# Wearable_sensor_v2_0.net
KiCad netlist of a schematic drawn in Altium Designer
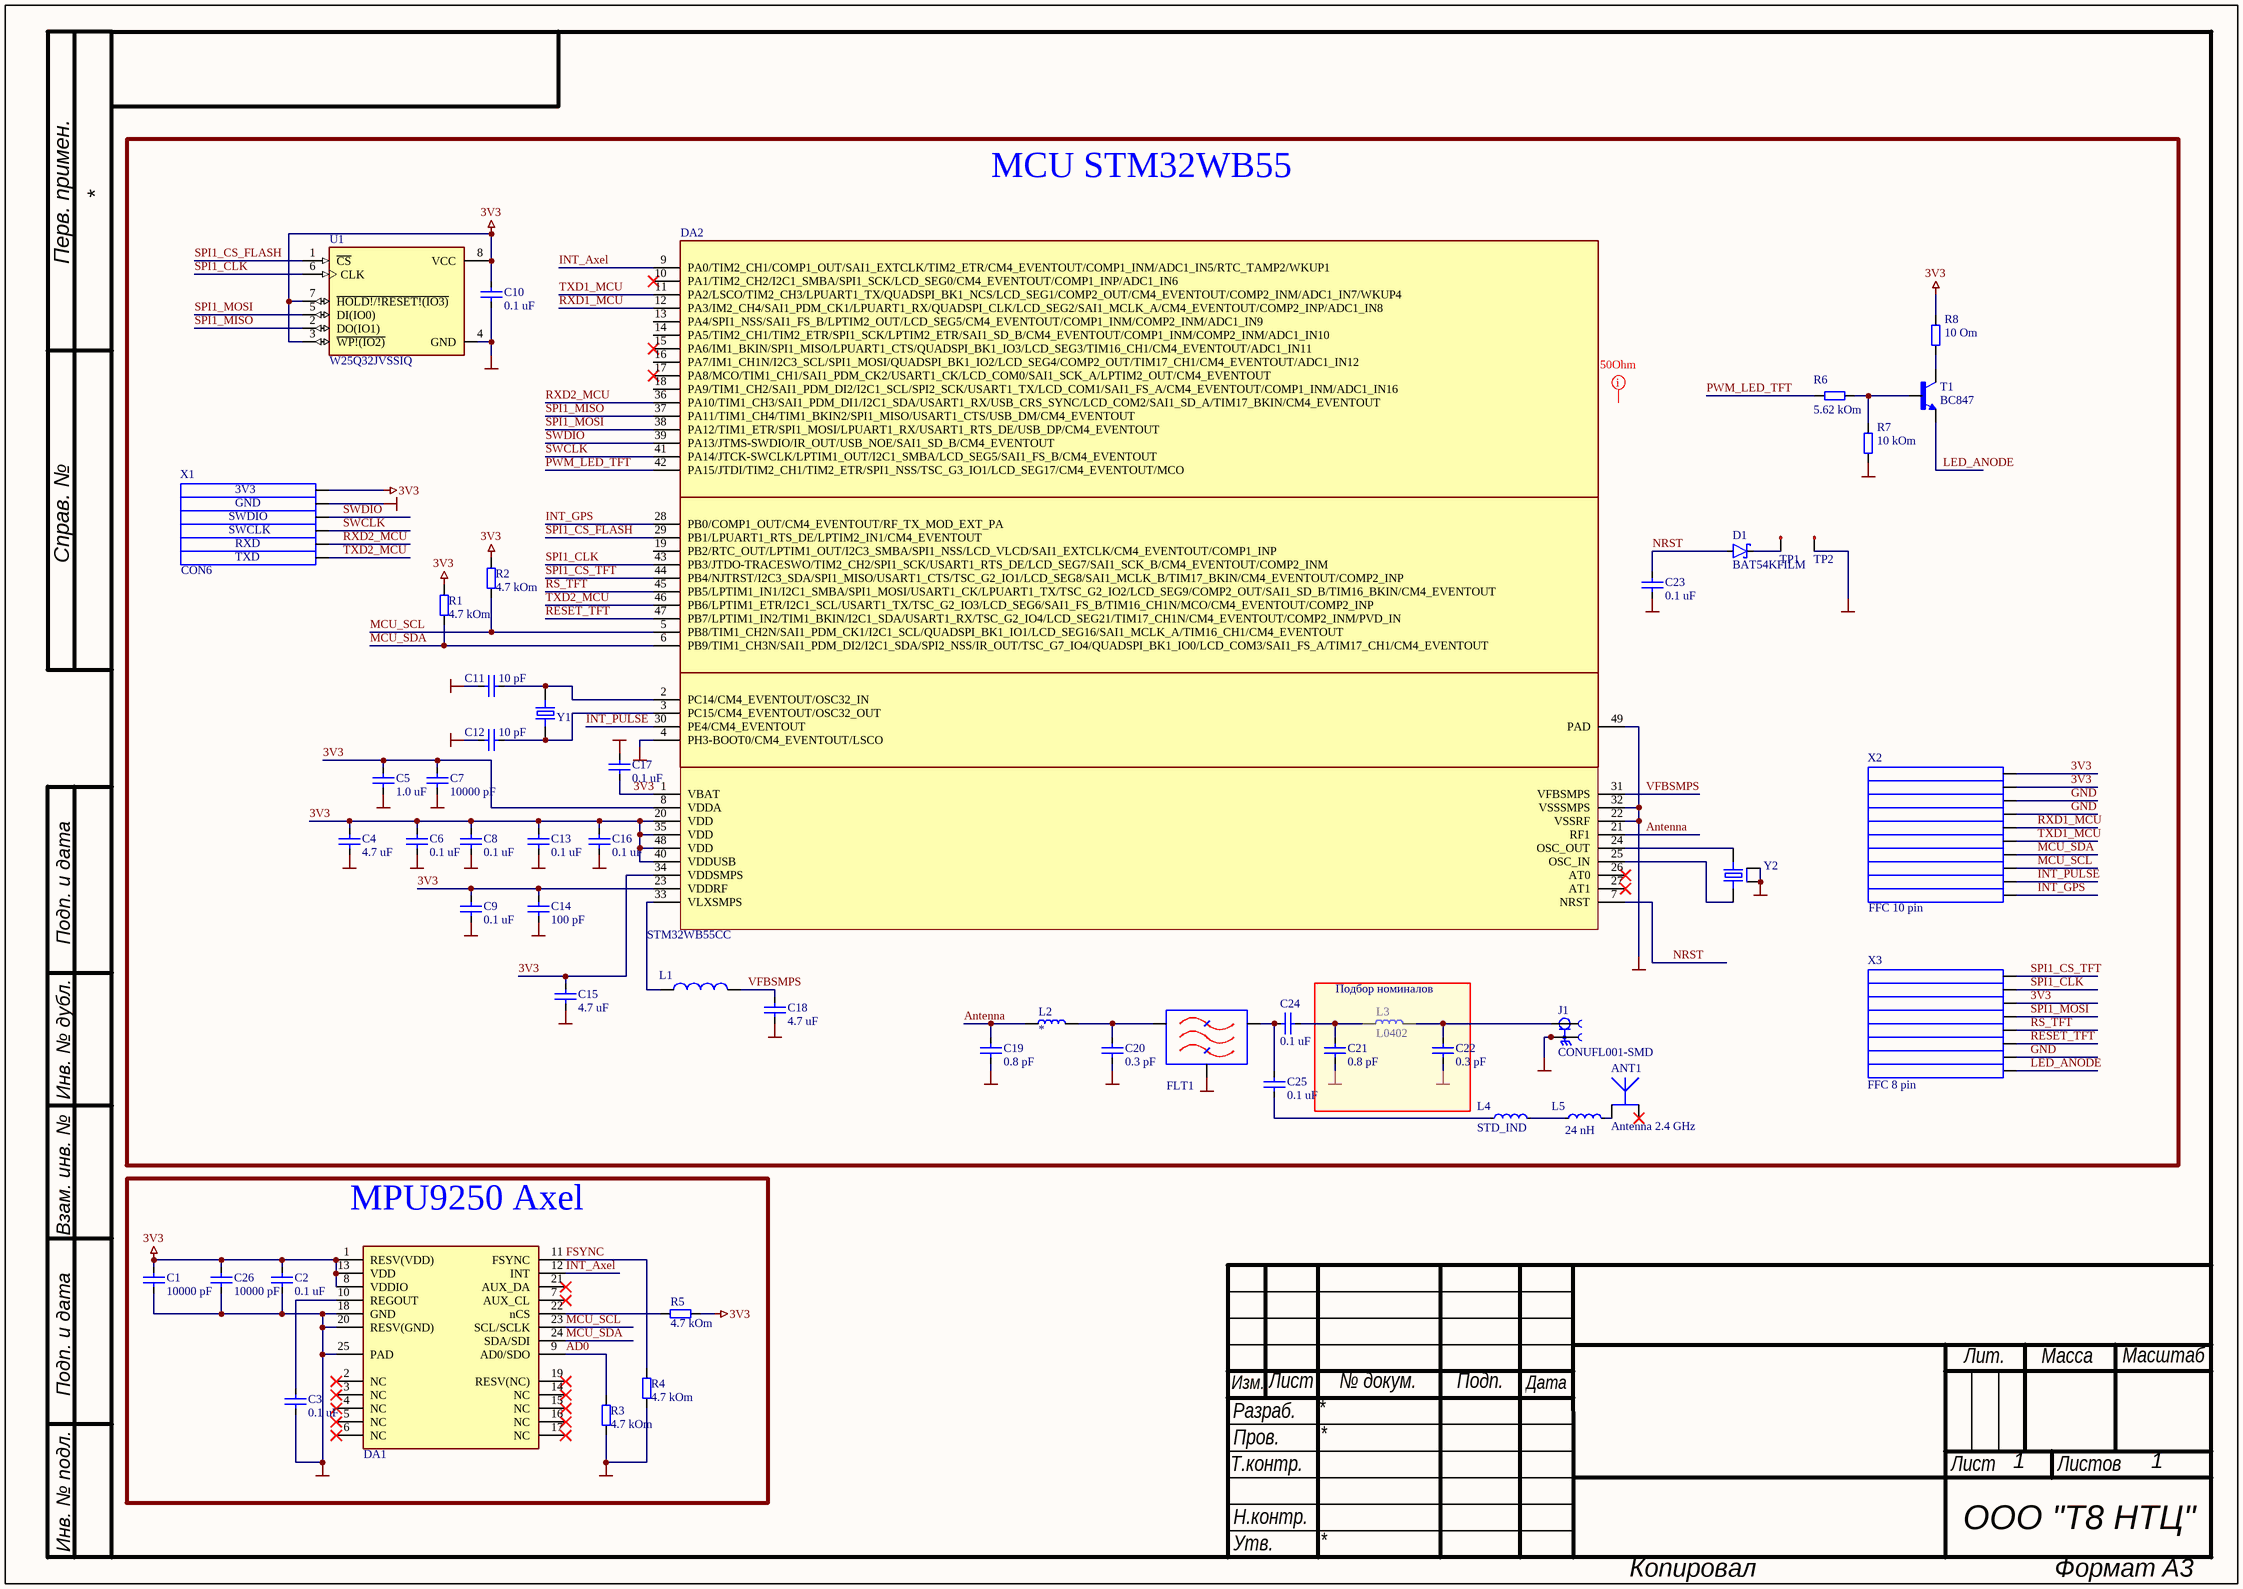
[diagram p0: Wearable_sensor_v2.0.SchDoc]

(export (version "E")
  (design (tool "Eeschema 10.0.6"))
  (components
    (comp (ref "ANT1")
      (value "Antenna 2.4 GHz")
      (footprint "RFANT3216120A5T")
      (libsource (lib "SCH_Wearing_sensor") (part "Antenna 2.4"))
    )
    (comp (ref "C1")
      (value "10000 pF")
      (footprint "CAPC1005X55N")
      (fields
        (field (name "MANUFACTURERPARTNUMBER") "GRM155R71H103KA88D")
        (field (name "MANUFACTURER") "muRata")
        (field (name "Comment") "STD_CAP")
        (field (name "AUTHORMODIFICATION_COMP") "anosova")
      )
      (libsource (lib "Altium_lib") (part "STD_CAP"))
    )
    (comp (ref "C2")
      (value "0.1 uF")
      (footprint "CAPC1005X55N")
      (fields
        (field (name "MANUFACTURERPARTNUMBER") "GRM155R71H104KE14D")
        (field (name "MANUFACTURER") "muRata")
        (field (name "Comment") "STD_CAP")
        (field (name "AUTHORCREATION_COMP") "altium_lib_sch_p")
        (field (name "AUTHORMODIFICATION_COMP") "anosova")
      )
      (libsource (lib "Altium_lib") (part "STD_CAP"))
    )
    (comp (ref "C3")
      (value "0.1 uF")
      (footprint "CAPC1005X55N")
      (fields
        (field (name "MANUFACTURERPARTNUMBER") "GRM155R71H104KE14D")
        (field (name "MANUFACTURER") "muRata")
        (field (name "Comment") "STD_CAP")
        (field (name "AUTHORCREATION_COMP") "altium_lib_sch_p")
        (field (name "AUTHORMODIFICATION_COMP") "anosova")
      )
      (libsource (lib "Altium_lib") (part "STD_CAP"))
    )
    (comp (ref "C4")
      (value "4.7 uF")
      (footprint "CAPC1005X55N")
      (fields
        (field (name "MANUFACTURERPARTNUMBER") "GRM155R60J475M")
        (field (name "MANUFACTURER") "muRata")
        (field (name "Comment") "STD_CAP")
        (field (name "AUTHORCREATION_COMP") "asergeev")
        (field (name "AUTHORMODIFICATION_COMP") "anosova")
      )
      (libsource (lib "Altium_lib") (part "STD_CAP"))
    )
    (comp (ref "C5")
      (value "1.0 uF")
      (footprint "CAPC1005X55N")
      (fields
        (field (name "MANUFACTURERPARTNUMBER") "GRM155R61A105K")
        (field (name "MANUFACTURER") "muRata")
        (field (name "Comment") "STD_CAP")
        (field (name "AUTHORCREATION_COMP") "asergeev")
        (field (name "AUTHORMODIFICATION_COMP") "anosova")
      )
      (libsource (lib "Altium_lib") (part "STD_CAP"))
    )
    (comp (ref "C6")
      (value "0.1 uF")
      (footprint "CAPC1005X55N")
      (fields
        (field (name "MANUFACTURERPARTNUMBER") "GRM155R71H104KE14D")
        (field (name "MANUFACTURER") "muRata")
        (field (name "Comment") "STD_CAP")
        (field (name "AUTHORCREATION_COMP") "altium_lib_sch_p")
        (field (name "AUTHORMODIFICATION_COMP") "anosova")
      )
      (libsource (lib "Altium_lib") (part "STD_CAP"))
    )
    (comp (ref "C7")
      (value "10000 pF")
      (footprint "CAPC1005X55N")
      (fields
        (field (name "MANUFACTURERPARTNUMBER") "GRM155R71H103KA88D")
        (field (name "MANUFACTURER") "muRata")
        (field (name "Comment") "STD_CAP")
        (field (name "AUTHORMODIFICATION_COMP") "anosova")
      )
      (libsource (lib "Altium_lib") (part "STD_CAP"))
    )
    (comp (ref "C8")
      (value "0.1 uF")
      (footprint "CAPC1005X55N")
      (fields
        (field (name "MANUFACTURERPARTNUMBER") "GRM155R71H104KE14D")
        (field (name "MANUFACTURER") "muRata")
        (field (name "Comment") "STD_CAP")
        (field (name "AUTHORCREATION_COMP") "altium_lib_sch_p")
        (field (name "AUTHORMODIFICATION_COMP") "anosova")
      )
      (libsource (lib "Altium_lib") (part "STD_CAP"))
    )
    (comp (ref "C9")
      (value "0.1 uF")
      (footprint "CAPC1005X55N")
      (fields
        (field (name "MANUFACTURERPARTNUMBER") "GRM155R71H104KE14D")
        (field (name "MANUFACTURER") "muRata")
        (field (name "Comment") "STD_CAP")
        (field (name "AUTHORCREATION_COMP") "altium_lib_sch_p")
        (field (name "AUTHORMODIFICATION_COMP") "anosova")
      )
      (libsource (lib "Altium_lib") (part "STD_CAP"))
    )
    (comp (ref "C10")
      (value "0.1 uF")
      (footprint "CAPC1005X55N")
      (fields
        (field (name "MANUFACTURERPARTNUMBER") "GRM155R71H104KE14D")
        (field (name "MANUFACTURER") "muRata")
        (field (name "Comment") "STD_CAP")
        (field (name "AUTHORCREATION_COMP") "altium_lib_sch_p")
        (field (name "AUTHORMODIFICATION_COMP") "anosova")
      )
      (libsource (lib "Altium_lib") (part "STD_CAP"))
    )
    (comp (ref "C11")
      (value "10 pF")
      (footprint "CAPC1005X55N")
      (fields
        (field (name "MANUFACTURERPARTNUMBER") "GRM1555C1H100GA01D")
        (field (name "MANUFACTURER") "muRata")
        (field (name "Comment") "STD_CAP")
        (field (name "AUTHORMODIFICATION_COMP") "anosova")
      )
      (libsource (lib "Altium_lib") (part "STD_CAP"))
    )
    (comp (ref "C12")
      (value "10 pF")
      (footprint "CAPC1005X55N")
      (fields
        (field (name "MANUFACTURERPARTNUMBER") "GRM1555C1H100GA01D")
        (field (name "MANUFACTURER") "muRata")
        (field (name "Comment") "STD_CAP")
        (field (name "AUTHORMODIFICATION_COMP") "anosova")
      )
      (libsource (lib "Altium_lib") (part "STD_CAP"))
    )
    (comp (ref "C13")
      (value "0.1 uF")
      (footprint "CAPC1005X55N")
      (fields
        (field (name "MANUFACTURERPARTNUMBER") "GRM155R71H104KE14D")
        (field (name "MANUFACTURER") "muRata")
        (field (name "Comment") "STD_CAP")
        (field (name "AUTHORCREATION_COMP") "altium_lib_sch_p")
        (field (name "AUTHORMODIFICATION_COMP") "anosova")
      )
      (libsource (lib "Altium_lib") (part "STD_CAP"))
    )
    (comp (ref "C14")
      (value "100 pF")
      (footprint "CAPC1005X55N")
      (fields
        (field (name "MANUFACTURERPARTNUMBER") "GRM1555C1H101GA01D")
        (field (name "MANUFACTURER") "muRata")
        (field (name "Comment") "STD_CAP")
        (field (name "AUTHORMODIFICATION_COMP") "anosova")
      )
      (libsource (lib "Altium_lib") (part "STD_CAP"))
    )
    (comp (ref "C15")
      (value "4.7 uF")
      (footprint "CAPC1005X55N")
      (fields
        (field (name "MANUFACTURERPARTNUMBER") "GRM155R60J475M")
        (field (name "MANUFACTURER") "muRata")
        (field (name "Comment") "STD_CAP")
        (field (name "AUTHORCREATION_COMP") "asergeev")
        (field (name "AUTHORMODIFICATION_COMP") "anosova")
      )
      (libsource (lib "Altium_lib") (part "STD_CAP"))
    )
    (comp (ref "C16")
      (value "0.1 uF")
      (footprint "CAPC1005X55N")
      (fields
        (field (name "MANUFACTURERPARTNUMBER") "GRM155R71H104KE14D")
        (field (name "MANUFACTURER") "muRata")
        (field (name "Comment") "STD_CAP")
        (field (name "AUTHORCREATION_COMP") "altium_lib_sch_p")
        (field (name "AUTHORMODIFICATION_COMP") "anosova")
      )
      (libsource (lib "Altium_lib") (part "STD_CAP"))
    )
    (comp (ref "C17")
      (value "0.1 uF")
      (footprint "CAPC1005X55N")
      (fields
        (field (name "MANUFACTURERPARTNUMBER") "GRM155R71H104KE14D")
        (field (name "MANUFACTURER") "muRata")
        (field (name "Comment") "STD_CAP")
        (field (name "AUTHORCREATION_COMP") "altium_lib_sch_p")
        (field (name "AUTHORMODIFICATION_COMP") "anosova")
      )
      (libsource (lib "Altium_lib") (part "STD_CAP"))
    )
    (comp (ref "C18")
      (value "4.7 uF")
      (footprint "CAPC1005X55N")
      (fields
        (field (name "MANUFACTURERPARTNUMBER") "GRM155R60J475M")
        (field (name "MANUFACTURER") "muRata")
        (field (name "Comment") "STD_CAP")
        (field (name "AUTHORCREATION_COMP") "asergeev")
        (field (name "AUTHORMODIFICATION_COMP") "anosova")
      )
      (libsource (lib "Altium_lib") (part "STD_CAP"))
    )
    (comp (ref "C19")
      (value "0.8 pF")
      (footprint "CAPC1005X55N")
      (fields
        (field (name "MANUFACTURERPARTNUMBER") "GRM1555C1HR80WA01D")
        (field (name "MANUFACTURER") "muRata")
        (field (name "Comment") "STD_CAP")
        (field (name "AUTHORMODIFICATION_COMP") "anosova")
      )
      (libsource (lib "Altium_lib") (part "STD_CAP"))
    )
    (comp (ref "C20")
      (value "0.3 pF")
      (footprint "CAPC1005X55N")
      (fields
        (field (name "MANUFACTURERPARTNUMBER") "GRM1555C1HR30WA01D")
        (field (name "MANUFACTURER") "muRata")
        (field (name "Comment") "STD_CAP")
        (field (name "AUTHORMODIFICATION_COMP") "anosova")
      )
      (libsource (lib "Altium_lib") (part "STD_CAP"))
    )
    (comp (ref "C21")
      (value "0.8 pF")
      (footprint "CAPC1005X55N")
      (fields
        (field (name "MANUFACTURERPARTNUMBER") "GRM1555C1HR80WA01D")
        (field (name "MANUFACTURER") "muRata")
        (field (name "Comment") "STD_CAP")
        (field (name "AUTHORMODIFICATION_COMP") "anosova")
      )
      (libsource (lib "Altium_lib") (part "STD_CAP"))
    )
    (comp (ref "C22")
      (value "0.3 pF")
      (footprint "CAPC1005X55N")
      (fields
        (field (name "MANUFACTURERPARTNUMBER") "GRM1555C1HR30WA01D")
        (field (name "MANUFACTURER") "muRata")
        (field (name "Comment") "STD_CAP")
        (field (name "AUTHORMODIFICATION_COMP") "anosova")
      )
      (libsource (lib "Altium_lib") (part "STD_CAP"))
    )
    (comp (ref "C23")
      (value "0.1 uF")
      (footprint "CAPC1005X55N")
      (fields
        (field (name "MANUFACTURERPARTNUMBER") "GRM155R71H104KE14D")
        (field (name "MANUFACTURER") "muRata")
        (field (name "Comment") "STD_CAP")
        (field (name "AUTHORCREATION_COMP") "altium_lib_sch_p")
        (field (name "AUTHORMODIFICATION_COMP") "anosova")
      )
      (libsource (lib "Altium_lib") (part "STD_CAP"))
    )
    (comp (ref "C24")
      (value "0.1 uF")
      (footprint "CAPC1005X55N")
      (fields
        (field (name "MANUFACTURERPARTNUMBER") "CC0402KRX7R8BB104")
        (field (name "MANUFACTURER") "Yageo")
        (field (name "Comment") "STD_CAP")
        (field (name "AUTHORCREATION_COMP") "anosova")
        (field (name "AUTHORMODIFICATION_COMP") "anosova")
      )
      (libsource (lib "Altium_lib") (part "STD_CAP"))
    )
    (comp (ref "C25")
      (value "0.1 uF")
      (footprint "CAPC1005X55N")
      (fields
        (field (name "MANUFACTURERPARTNUMBER") "CC0402KRX7R8BB104")
        (field (name "MANUFACTURER") "Yageo")
        (field (name "Comment") "STD_CAP")
        (field (name "AUTHORCREATION_COMP") "anosova")
        (field (name "AUTHORMODIFICATION_COMP") "anosova")
      )
      (libsource (lib "Altium_lib") (part "STD_CAP"))
    )
    (comp (ref "C26")
      (value "10000 pF")
      (footprint "CAPC1005X55N:CAPC1005X55N")
      (fields
        (field (name "MANUFACTURERPARTNUMBER") "GRM155R71H103KA88D")
        (field (name "MANUFACTURER") "muRata")
        (field (name "Comment") "STD_CAP")
        (field (name "AUTHORMODIFICATION_COMP") "anosova")
      )
      (libsource (lib "Altium_lib") (part "STD_CAP"))
    )
    (comp (ref "D1")
      (value "BAT54KFILM")
      (footprint "SOD523:SOD523")
      (description "Diode Schottky")
      (fields (field (name "MANUFACTURER") "STMicroelectronics"))
      (libsource (lib "SCH_Wearing_sensor") (part "BAT54KFILM"))
    )
    (comp (ref "DA1")
      (value "IventSense_MPU-9250")
      (footprint "QFN24 3x3x1mm")
      (fields
        (field (name "MANUFACTURERPARTNUMBER") "MPU-9250")
        (field (name "MANUFACTURER") "InvenSense")
        (field (name "COMPONENTLINK1URL") "D:\\HSE\\Трекер физ состояния\\Help\\mpu9265.pdf")
        (field (name "HELP") "D:\\HSE\\Трекер физ состояния\\Help\\mpu9265.pdf")
      )
      (libsource (lib "SCH_Wearing_sensor") (part "MPU-9250"))
    )
    (comp (ref "DA2")
      (value "STM32WB55CC")
      (footprint "UFQFPN48")
      (fields
        (field (name "MANUFACTURER") "STMicroelectronics")
        (field (name "MANUFACTURERPARTNUMBER") "STM32WB55CC")
        (field (name "COMPONENTLINK1URL") "D:\\HSE\\Трекер физ состояния\\Help\\stm32wb55cc.pdf")
      )
      (libsource (lib "SCH_Wearing_sensor") (part "STM32WB55"))
    )
    (comp (ref "FLT1")
      (value "DEA162450-1260B2")
      (footprint "FIL_DEA160915LT-1169")
      (description "Band Pass Filter TDK DEA162450-1260B2")
      (fields (field (name "MANUFACTURER") "TDK"))
      (libsource (lib "SCH_Wearing_sensor") (part "DEA162450-1260B2"))
    )
    (comp (ref "J1")
      (value "CONUFL001-SMD")
      (footprint "LINX_CONUFL001-SMD")
      (fields
        (field (name "MANUFACTURER") "TE Connectivity")
        (field (name "MANUFACTURERPARTNUMBER") "1909763-1")
      )
      (libsource (lib "SCH_Wearing_sensor") (part "CONUFL001-SMD"))
    )
    (comp (ref "L1")
      (value "MLF2012E100KT000")
      (footprint "INDC2012X145N")
      (description "10 ÂµH Shielded Multilayer Inductor 15 mA 800mOhm Max 0805 (2012 Metric)")
      (fields (field (name "MF") "TDK"))
      (libsource (lib "SCH_Wearing_sensor") (part "MLF2012E100KT000"))
    )
    (comp (ref "L2")
      (value "L0402")
      (footprint "L0402")
      (description "Fixed Inductors 0402")
      (fields
        (field (name "MF") "Murata")
        (field (name "MP") "LQG15HN1N5S00D")
        (field (name "ALTIUM_VALUE") "*")
      )
      (libsource (lib "SCH_Wearing_sensor") (part "L0402"))
    )
    (comp (ref "L3")
      (value "L0402")
      (footprint "L0402")
      (description "Fixed Inductors 0402")
      (fields (field (name "MF") "Murata") (field (name "MP") "LQG15HN1N5S00D"))
      (libsource (lib "SCH_Wearing_sensor") (part "L0402"))
    )
    (comp (ref "L4")
      (value "STD_IND")
      (footprint "RESC1005X40N")
      (fields
        (field (name "MANUFACTURERPARTNUMBER") "LQW15AN24NG00")
        (field (name "MANUFACTURER") "muRata")
        (field (name "AUTHORCREATION_COMP") "altium_lib_sch_p")
        (field (name "AUTHORMODIFICATION_COMP") "altium_lib_sch_p")
      )
      (libsource (lib "Altium_lib") (part "STD_IND"))
    )
    (comp (ref "L5")
      (value "24 nH")
      (footprint "RESC1005X40N")
      (fields
        (field (name "MANUFACTURERPARTNUMBER") "LQW15AN24NG00")
        (field (name "MANUFACTURER") "muRata")
        (field (name "Comment") "STD_IND")
        (field (name "AUTHORCREATION_COMP") "altium_lib_sch_p")
        (field (name "AUTHORMODIFICATION_COMP") "altium_lib_sch_p")
      )
      (libsource (lib "Altium_lib") (part "STD_IND"))
    )
    (comp (ref "R1")
      (value "4.7 kOm")
      (footprint "RESC1005X40N")
      (fields
        (field (name "MANUFACTURERPARTNUMBER") "RC0402JR-074K7L")
        (field (name "MANUFACTURER") "Yageo")
        (field (name "Comment") "STD_RES")
      )
      (libsource (lib "Altium_lib") (part "STD_RES"))
    )
    (comp (ref "R2")
      (value "4.7 kOm")
      (footprint "RESC1005X40N")
      (fields
        (field (name "MANUFACTURERPARTNUMBER") "RC0402JR-074K7L")
        (field (name "MANUFACTURER") "Yageo")
        (field (name "Comment") "STD_RES")
      )
      (libsource (lib "Altium_lib") (part "STD_RES"))
    )
    (comp (ref "R3")
      (value "4.7 kOm")
      (footprint "RESC1005X40N")
      (fields
        (field (name "MANUFACTURERPARTNUMBER") "RC0402JR-074K7L")
        (field (name "MANUFACTURER") "Yageo")
        (field (name "Comment") "STD_RES")
      )
      (libsource (lib "Altium_lib") (part "STD_RES"))
    )
    (comp (ref "R4")
      (value "4.7 kOm")
      (footprint "RESC1005X40N")
      (fields
        (field (name "MANUFACTURERPARTNUMBER") "RC0402JR-074K7L")
        (field (name "MANUFACTURER") "Yageo")
        (field (name "Comment") "STD_RES")
      )
      (libsource (lib "Altium_lib") (part "STD_RES"))
    )
    (comp (ref "R5")
      (value "4.7 kOm")
      (footprint "RESC1005X40N")
      (fields
        (field (name "MANUFACTURERPARTNUMBER") "RC0402JR-074K7L")
        (field (name "MANUFACTURER") "Yageo")
        (field (name "Comment") "STD_RES")
      )
      (libsource (lib "") (part "STD_RES_1"))
    )
    (comp (ref "R6")
      (value "5.62 kOm")
      (footprint "RESC1005X40N")
      (fields
        (field (name "MANUFACTURERPARTNUMBER") "RC0402FR-075K62L")
        (field (name "MANUFACTURER") "Yageo")
        (field (name "Comment") "STD_RES")
      )
      (libsource (lib "") (part "STD_RES_1"))
    )
    (comp (ref "R7")
      (value "10 kOm")
      (footprint "RESC1005X40N")
      (fields
        (field (name "MANUFACTURERPARTNUMBER") "RC0402FR-0710K0L")
        (field (name "MANUFACTURER") "Yageo")
        (field (name "Comment") "STD_RES")
      )
      (libsource (lib "Altium_lib") (part "STD_RES"))
    )
    (comp (ref "R8")
      (value "10 Om")
      (footprint "RESC1005X40N")
      (fields
        (field (name "MANUFACTURERPARTNUMBER") "RC0402FR-0710R0L")
        (field (name "MANUFACTURER") "Yageo")
        (field (name "Comment") "STD_RES")
      )
      (libsource (lib "Altium_lib") (part "STD_RES"))
    )
    (comp (ref "T1")
      (value "BC847")
      (footprint "SOT23")
      (description "<b>NPN TRANSISTOR</b>")
      (libsource (lib "SCH_Wearing_sensor") (part "BC847"))
    )
    (comp (ref "TP1")
      (value "Test Point")
      (footprint "Test point")
      (libsource (lib "SCH_Wearing_sensor") (part "Test Point"))
    )
    (comp (ref "TP2")
      (value "Test Point")
      (footprint "Test point")
      (libsource (lib "SCH_Wearing_sensor") (part "Test Point"))
    )
    (comp (ref "U1")
      (value "W25Q32JVSSIQ")
      (footprint "SOIC127P790X216-8N")
      (description "FLASH - NOR Memory IC 32Mb _4M x 8_ SPI - Quad I/O 133MHz 8-SOIC")
      (fields (field (name "MF") "Winbond"))
      (libsource (lib "SCH_Wearing_sensor") (part "W25Q32JVSSIQ"))
    )
    (comp (ref "X1")
      (value "CON6")
      (footprint "CON6 cabel")
      (description "Коннектор 6-ти контактный")
      (fields (field (name "MANUFACTURERPARTNUMBER") "PLS-4") (field (name "MANUFACTURER") "Connfly"))
      (libsource (lib "SCH_Wearing_sensor") (part "CON6"))
    )
    (comp (ref "X2")
      (value "FFC 10 pin")
      (footprint "SAMTEC_ZF5S-10-01-T-WT")
      (description "FFC connector 8 pin")
      (libsource (lib "SCH_Wearing_sensor") (part "FFC 10 pin"))
    )
    (comp (ref "X3")
      (value "FFC 8 pin")
      (footprint "68710814022")
      (description "FFC connector 8 pin")
      (libsource (lib "SCH_Wearing_sensor") (part "FFC 8 pin"))
    )
    (comp (ref "Y1")
      (value "NX2012SA-32.768K-STD-MUB-1_1")
      (footprint "XTAL_NX2012SA-32.768K-STD-MUB-1")
      (description "32.768 kHz Â±20ppm Crystal 12.5pF 80 kOhms 2-SMD, No Lead")
      (fields (field (name "MF") "NDK America,") (field (name "MP") "NX2012SA-32.768K-STD-MUB-1"))
      (libsource (lib "SCH_Wearing_sensor") (part "NX2012SA-32.768K-STD-MUB-1_1"))
    )
    (comp (ref "Y2")
      (value "NX2016_32M")
      (footprint "NX2016_32M")
      (description "32 MHz  Crystal")
      (fields (field (name "MF") "NDK America,") (field (name "MP") "NX2012SA-32.768K-STD-MUB-1"))
      (libsource (lib "SCH_Wearing_sensor") (part "NX2016_32M"))
    )
  )
  (nets
    (net (code "1") (name "/AD0") (class "Default")
      (node (ref "DA1") (pin "9") (pinfunction "AD0/SDO_9") (pintype "passive"))
      (node (ref "R3") (pin "2") (pinfunction "2_2") (pintype "passive"))
    )
    (net (code "2") (name "/Antenna") (class "Default")
      (node (ref "C19") (pin "1") (pinfunction "1_1") (pintype "passive"))
      (node (ref "DA2") (pin "21") (pinfunction "RF1_21") (pintype "passive"))
      (node (ref "L2") (pin "1") (pinfunction "1_1") (pintype "passive"))
    )
    (net (code "3") (name "/FSYNC") (class "Default")
      (node (ref "DA1") (pin "11") (pinfunction "FSYNC_11") (pintype "passive"))
      (node (ref "R4") (pin "2") (pinfunction "2_2") (pintype "passive"))
    )
    (net (code "4") (name "/INT_Axel") (class "Default")
      (node (ref "DA1") (pin "12") (pinfunction "INT_12") (pintype "passive"))
      (node (ref "DA2") (pin "9") (pinfunction "PA0/TIM2_CH1/COMP1_OUT/SAI1_EXTCLK/TIM2_ETR/CM4_EVENTOUT/COMP1_INM/ADC1_IN5/RTC_TAMP2/WKUP1_9") (pintype "passive"))
    )
    (net (code "5") (name "/INT_GPS") (class "Default")
      (node (ref "DA2") (pin "28") (pinfunction "PB0/COMP1_OUT/CM4_EVENTOUT/RF_TX_MOD_EXT_PA_28") (pintype "passive"))
      (node (ref "X2") (pin "10") (pintype "passive"))
    )
    (net (code "6") (name "/INT_PULSE") (class "Default")
      (node (ref "DA2") (pin "30") (pinfunction "PE4/CM4_EVENTOUT_30") (pintype "passive"))
      (node (ref "X2") (pin "9") (pintype "passive"))
    )
    (net (code "7") (name "/LED_ANODE") (class "Default")
      (node (ref "T1") (pin "2") (pinfunction "E_2") (pintype "passive"))
      (node (ref "X3") (pin "8") (pintype "passive"))
    )
    (net (code "8") (name "/MCU_SCL") (class "Default")
      (node (ref "DA1") (pin "23") (pinfunction "SCL/SCLK_23") (pintype "passive"))
      (node (ref "DA2") (pin "5") (pinfunction "PB8/TIM1_CH2N/SAI1_PDM_CK1/I2C1_SCL/QUADSPI_BK1_IO1/LCD_SEG16/SAI1_MCLK_A/TIM16_CH1/CM4_EVENTOUT_5") (pintype "passive"))
      (node (ref "R2") (pin "1") (pinfunction "1_1") (pintype "passive"))
      (node (ref "X2") (pin "8") (pintype "passive"))
    )
    (net (code "9") (name "/MCU_SDA") (class "Default")
      (node (ref "DA1") (pin "24") (pinfunction "SDA/SDI_24") (pintype "passive"))
      (node (ref "DA2") (pin "6") (pinfunction "PB9/TIM1_CH3N/SAI1_PDM_DI2/I2C1_SDA/SPI2_NSS/IR_OUT/TSC_G7_IO4/QUADSPI_BK1_IO0/LCD_COM3/SAI1_FS_A/TIM17_CH1/CM4_EVENTOUT_6") (pintype "passive"))
      (node (ref "R1") (pin "1") (pinfunction "1_1") (pintype "passive"))
      (node (ref "X2") (pin "7") (pintype "passive"))
    )
    (net (code "10") (name "/NRST") (class "Default")
      (node (ref "C23") (pin "1") (pinfunction "1_1") (pintype "passive"))
      (node (ref "D1") (pin "2") (pinfunction "A_2") (pintype "passive"))
      (node (ref "DA2") (pin "7") (pinfunction "NRST_7") (pintype "passive"))
    )
    (net (code "11") (name "/PWM_LED_TFT") (class "Default")
      (node (ref "DA2") (pin "42") (pinfunction "PA15/JTDI/TIM2_CH1/TIM2_ETR/SPI1_NSS/TSC_G3_IO1/LCD_SEG17/CM4_EVENTOUT/MCO_42") (pintype "passive"))
      (node (ref "R6") (pin "2") (pinfunction "2_2") (pintype "passive"))
    )
    (net (code "12") (name "/RESET_TFT") (class "Default")
      (node (ref "DA2") (pin "47") (pinfunction "PB7/LPTIM1_IN2/TIM1_BKIN/I2C1_SDA/USART1_RX/TSC_G2_IO4/LCD_SEG21/TIM17_CH1N/CM4_EVENTOUT/COMP2_INM/PVD_IN_47") (pintype "passive"))
      (node (ref "X3") (pin "6") (pintype "passive"))
    )
    (net (code "13") (name "/RS_TFT") (class "Default")
      (node (ref "DA2") (pin "45") (pinfunction "PB5/LPTIM1_IN1/I2C1_SMBA/SPI1_MOSI/USART1_CK/LPUART1_TX/TSC_G2_IO2/LCD_SEG9/COMP2_OUT/SAI1_SD_B/TIM16_BKIN/CM4_EVENTOUT_45") (pintype "passive"))
      (node (ref "X3") (pin "5") (pintype "passive"))
    )
    (net (code "14") (name "/RXD1_MCU") (class "Default")
      (node (ref "DA2") (pin "12") (pinfunction "PA3/IM2_CH4/SAI1_PDM_CK1/LPUART1_RX/QUADSPI_CLK/LCD_SEG2/SAI1_MCLK_A/CM4_EVENTOUT/COMP2_INP/ADC1_IN8_12") (pintype "passive"))
      (node (ref "X2") (pin "5") (pintype "passive"))
    )
    (net (code "15") (name "/RXD2_MCU") (class "Default")
      (node (ref "DA2") (pin "36") (pinfunction "PA10/TIM1_CH3/SAI1_PDM_DI1/I2C1_SDA/USART1_RX/USB_CRS_SYNC/LCD_COM2/SAI1_SD_A/TIM17_BKIN/CM4_EVENTOUT_36") (pintype "passive"))
      (node (ref "X1") (pin "5") (pintype "passive"))
    )
    (net (code "16") (name "/SPI1_CLK") (class "Default")
      (node (ref "DA2") (pin "43") (pinfunction "PB3/JTDO-TRACESWO/TIM2_CH2/SPI1_SCK/USART1_RTS_DE/LCD_SEG7/SAI1_SCK_B/CM4_EVENTOUT/COMP2_INM_43") (pintype "passive"))
      (node (ref "U1") (pin "6") (pinfunction "CLK_6") (pintype "input"))
      (node (ref "X3") (pin "2") (pintype "passive"))
    )
    (net (code "17") (name "/SPI1_CS_FLASH") (class "Default")
      (node (ref "DA2") (pin "29") (pinfunction "PB1/LPUART1_RTS_DE/LPTIM2_IN1/CM4_EVENTOUT_29") (pintype "passive"))
      (node (ref "U1") (pin "1") (pinfunction "~{CS}_1") (pintype "input"))
    )
    (net (code "18") (name "/SPI1_CS_TFT") (class "Default")
      (node (ref "DA2") (pin "44") (pinfunction "PB4/NJTRST/I2C3_SDA/SPI1_MISO/USART1_CTS/TSC_G2_IO1/LCD_SEG8/SAI1_MCLK_B/TIM17_BKIN/CM4_EVENTOUT/COMP2_INP_44") (pintype "passive"))
      (node (ref "X3") (pin "1") (pintype "passive"))
    )
    (net (code "19") (name "/SPI1_MISO") (class "Default")
      (node (ref "DA2") (pin "37") (pinfunction "PA11/TIM1_CH4/TIM1_BKIN2/SPI1_MISO/USART1_CTS/USB_DM/CM4_EVENTOUT_37") (pintype "passive"))
      (node (ref "U1") (pin "2") (pinfunction "DO(IO1)_2") (pintype "bidirectional"))
    )
    (net (code "20") (name "/SPI1_MOSI") (class "Default")
      (node (ref "DA2") (pin "38") (pinfunction "PA12/TIM1_ETR/SPI1_MOSI/LPUART1_RX/USART1_RTS_DE/USB_DP/CM4_EVENTOUT_38") (pintype "passive"))
      (node (ref "U1") (pin "5") (pinfunction "DI(IO0)_5") (pintype "bidirectional"))
      (node (ref "X3") (pin "4") (pintype "passive"))
    )
    (net (code "21") (name "/SWCLK") (class "Default")
      (node (ref "DA2") (pin "41") (pinfunction "PA14/JTCK-SWCLK/LPTIM1_OUT/I2C1_SMBA/LCD_SEG5/SAI1_FS_B/CM4_EVENTOUT_41") (pintype "passive"))
      (node (ref "X1") (pin "4") (pintype "passive"))
    )
    (net (code "22") (name "/SWDIO") (class "Default")
      (node (ref "DA2") (pin "39") (pinfunction "PA13/JTMS-SWDIO/IR_OUT/USB_NOE/SAI1_SD_B/CM4_EVENTOUT_39") (pintype "passive"))
      (node (ref "X1") (pin "3") (pintype "passive"))
    )
    (net (code "23") (name "/TXD1_MCU") (class "Default")
      (node (ref "DA2") (pin "11") (pinfunction "PA2/LSCO/TIM2_CH3/LPUART1_TX/QUADSPI_BK1_NCS/LCD_SEG1/COMP2_OUT/CM4_EVENTOUT/COMP2_INM/ADC1_IN7/WKUP4_11") (pintype "passive"))
      (node (ref "X2") (pin "6") (pintype "passive"))
    )
    (net (code "24") (name "/TXD2_MCU") (class "Default")
      (node (ref "DA2") (pin "46") (pinfunction "PB6/LPTIM1_ETR/I2C1_SCL/USART1_TX/TSC_G2_IO3/LCD_SEG6/SAI1_FS_B/TIM16_CH1N/MCO/CM4_EVENTOUT/COMP2_INP_46") (pintype "passive"))
      (node (ref "X1") (pin "6") (pintype "passive"))
    )
    (net (code "25") (name "/VFBSMPS") (class "Default")
      (node (ref "C18") (pin "1") (pinfunction "1_1") (pintype "passive"))
      (node (ref "DA2") (pin "31") (pinfunction "VFBSMPS_31") (pintype "passive"))
      (node (ref "L1") (pin "1") (pinfunction "1_1") (pintype "passive"))
    )
    (net (code "26") (name "3V3") (class "Default")
      (node (ref "C1") (pin "1") (pinfunction "1_1") (pintype "passive"))
      (node (ref "C10") (pin "1") (pinfunction "1_1") (pintype "passive"))
      (node (ref "C13") (pin "1") (pinfunction "1_1") (pintype "passive"))
      (node (ref "C14") (pin "1") (pinfunction "1_1") (pintype "passive"))
      (node (ref "C15") (pin "1") (pinfunction "1_1") (pintype "passive"))
      (node (ref "C16") (pin "1") (pinfunction "1_1") (pintype "passive"))
      (node (ref "C17") (pin "2") (pinfunction "2_2") (pintype "passive"))
      (node (ref "C2") (pin "1") (pinfunction "1_1") (pintype "passive"))
      (node (ref "C26") (pin "1") (pinfunction "1_1") (pintype "passive"))
      (node (ref "C4") (pin "1") (pinfunction "1_1") (pintype "passive"))
      (node (ref "C5") (pin "1") (pinfunction "1_1") (pintype "passive"))
      (node (ref "C6") (pin "1") (pinfunction "1_1") (pintype "passive"))
      (node (ref "C7") (pin "1") (pinfunction "1_1") (pintype "passive"))
      (node (ref "C8") (pin "1") (pinfunction "1_1") (pintype "passive"))
      (node (ref "C9") (pin "1") (pinfunction "1_1") (pintype "passive"))
      (node (ref "DA1") (pin "1") (pinfunction "RESV(VDD)_1") (pintype "passive"))
      (node (ref "DA1") (pin "13") (pinfunction "VDD_13") (pintype "passive"))
      (node (ref "DA1") (pin "8") (pinfunction "VDDIO_8") (pintype "passive"))
      (node (ref "DA2") (pin "1") (pinfunction "VBAT_1") (pintype "passive"))
      (node (ref "DA2") (pin "20") (pinfunction "VDD_20") (pintype "passive"))
      (node (ref "DA2") (pin "23") (pinfunction "VDDRF_23") (pintype "passive"))
      (node (ref "DA2") (pin "34") (pinfunction "VDDSMPS_34") (pintype "passive"))
      (node (ref "DA2") (pin "35") (pinfunction "VDD_35") (pintype "passive"))
      (node (ref "DA2") (pin "40") (pinfunction "VDDUSB_40") (pintype "passive"))
      (node (ref "DA2") (pin "48") (pinfunction "VDD_48") (pintype "passive"))
      (node (ref "DA2") (pin "8") (pinfunction "VDDA_8") (pintype "passive"))
      (node (ref "R1") (pin "2") (pinfunction "2_2") (pintype "passive"))
      (node (ref "R2") (pin "2") (pinfunction "2_2") (pintype "passive"))
      (node (ref "R5") (pin "1") (pinfunction "1_1") (pintype "passive"))
      (node (ref "R8") (pin "2") (pinfunction "2_2") (pintype "passive"))
      (node (ref "U1") (pin "3") (pinfunction "~{WP!(IO2)}_3") (pintype "bidirectional"))
      (node (ref "U1") (pin "7") (pinfunction "~{HOLD!/!RESET!(IO3)}_7") (pintype "bidirectional"))
      (node (ref "U1") (pin "8") (pinfunction "VCC_8") (pintype "power_in"))
      (node (ref "X1") (pin "1") (pintype "passive"))
      (node (ref "X2") (pin "1") (pintype "passive"))
      (node (ref "X2") (pin "2") (pintype "passive"))
      (node (ref "X3") (pin "3") (pintype "passive"))
    )
    (net (code "27") (name "GND") (class "Default")
      (node (ref "C1") (pin "2") (pinfunction "2_2") (pintype "passive"))
      (node (ref "C10") (pin "2") (pinfunction "2_2") (pintype "passive"))
      (node (ref "C11") (pin "2") (pinfunction "2_2") (pintype "passive"))
      (node (ref "C12") (pin "2") (pinfunction "2_2") (pintype "passive"))
      (node (ref "C13") (pin "2") (pinfunction "2_2") (pintype "passive"))
      (node (ref "C14") (pin "2") (pinfunction "2_2") (pintype "passive"))
      (node (ref "C15") (pin "2") (pinfunction "2_2") (pintype "passive"))
      (node (ref "C16") (pin "2") (pinfunction "2_2") (pintype "passive"))
      (node (ref "C17") (pin "1") (pinfunction "1_1") (pintype "passive"))
      (node (ref "C18") (pin "2") (pinfunction "2_2") (pintype "passive"))
      (node (ref "C19") (pin "2") (pinfunction "2_2") (pintype "passive"))
      (node (ref "C2") (pin "2") (pinfunction "2_2") (pintype "passive"))
      (node (ref "C20") (pin "2") (pinfunction "2_2") (pintype "passive"))
      (node (ref "C21") (pin "2") (pinfunction "2_2") (pintype "passive"))
      (node (ref "C22") (pin "2") (pinfunction "2_2") (pintype "passive"))
      (node (ref "C23") (pin "2") (pinfunction "2_2") (pintype "passive"))
      (node (ref "C26") (pin "2") (pinfunction "2_2") (pintype "passive"))
      (node (ref "C3") (pin "2") (pinfunction "2_2") (pintype "passive"))
      (node (ref "C4") (pin "2") (pinfunction "2_2") (pintype "passive"))
      (node (ref "C5") (pin "2") (pinfunction "2_2") (pintype "passive"))
      (node (ref "C6") (pin "2") (pinfunction "2_2") (pintype "passive"))
      (node (ref "C7") (pin "2") (pinfunction "2_2") (pintype "passive"))
      (node (ref "C8") (pin "2") (pinfunction "2_2") (pintype "passive"))
      (node (ref "C9") (pin "2") (pinfunction "2_2") (pintype "passive"))
      (node (ref "DA1") (pin "18") (pinfunction "GND_18") (pintype "passive"))
      (node (ref "DA1") (pin "20") (pinfunction "RESV(GND)_20") (pintype "passive"))
      (node (ref "DA1") (pin "25") (pinfunction "PAD_25") (pintype "passive"))
      (node (ref "DA2") (pin "22") (pinfunction "VSSRF_22") (pintype "passive"))
      (node (ref "DA2") (pin "32") (pinfunction "VSSSMPS_32") (pintype "passive"))
      (node (ref "DA2") (pin "4") (pinfunction "PH3-BOOT0/CM4_EVENTOUT/LSCO_4") (pintype "passive"))
      (node (ref "DA2") (pin "49") (pinfunction "PAD_49") (pintype "passive"))
      (node (ref "FLT1") (pin "2") (pintype "passive"))
      (node (ref "J1") (pin "2") (pinfunction "2_2") (pintype "passive"))
      (node (ref "J1") (pin "3") (pinfunction "2_3") (pintype "passive"))
      (node (ref "R3") (pin "1") (pinfunction "1_1") (pintype "passive"))
      (node (ref "R4") (pin "1") (pinfunction "1_1") (pintype "passive"))
      (node (ref "R7") (pin "1") (pinfunction "1_1") (pintype "passive"))
      (node (ref "TP2") (pin "1") (pintype "passive"))
      (node (ref "U1") (pin "4") (pinfunction "GND_4") (pintype "power_in"))
      (node (ref "X1") (pin "2") (pintype "passive"))
      (node (ref "X2") (pin "3") (pintype "passive"))
      (node (ref "X2") (pin "4") (pintype "passive"))
      (node (ref "X3") (pin "7") (pintype "passive"))
      (node (ref "Y2") (pin "1") (pinfunction "4_1") (pintype "passive"))
      (node (ref "Y2") (pin "3") (pinfunction "3_3") (pintype "passive"))
    )
    (net (code "28") (name "Net-(ANT1-0)") (class "Default")
      (node (ref "ANT1") (pin "1") (pinfunction "0_1") (pintype "passive"))
      (node (ref "L5") (pin "2") (pinfunction "2_2") (pintype "passive"))
    )
    (net (code "29") (name "Net-(C20-Pad1)") (class "Default")
      (node (ref "C20") (pin "1") (pinfunction "1_1") (pintype "passive"))
      (node (ref "FLT1") (pin "1") (pintype "passive"))
      (node (ref "L2") (pin "2") (pinfunction "2_2") (pintype "passive"))
    )
    (net (code "30") (name "Net-(C21-Pad1)") (class "Default")
      (node (ref "C21") (pin "1") (pinfunction "1_1") (pintype "passive"))
      (node (ref "C24") (pin "2") (pinfunction "2_2") (pintype "passive"))
      (node (ref "L3") (pin "1") (pinfunction "1_1") (pintype "passive"))
    )
    (net (code "31") (name "Net-(C22-Pad1)") (class "Default")
      (node (ref "C22") (pin "1") (pinfunction "1_1") (pintype "passive"))
      (node (ref "J1") (pin "1") (pinfunction "1_1") (pintype "passive"))
      (node (ref "L3") (pin "2") (pinfunction "2_2") (pintype "passive"))
    )
    (net (code "32") (name "Net-(C24-Pad1)") (class "Default")
      (node (ref "C24") (pin "1") (pinfunction "1_1") (pintype "passive"))
      (node (ref "C25") (pin "2") (pinfunction "2_2") (pintype "passive"))
      (node (ref "FLT1") (pin "3") (pintype "passive"))
    )
    (net (code "33") (name "Net-(C25-Pad1)") (class "Default")
      (node (ref "C25") (pin "1") (pinfunction "1_1") (pintype "passive"))
      (node (ref "L4") (pin "1") (pinfunction "1_1") (pintype "passive"))
    )
    (net (code "34") (name "Net-(D1-K)") (class "Default")
      (node (ref "D1") (pin "1") (pinfunction "K_1") (pintype "passive"))
      (node (ref "TP1") (pin "1") (pintype "passive"))
    )
    (net (code "35") (name "Net-(DA1-REGOUT)") (class "Default")
      (node (ref "C3") (pin "1") (pinfunction "1_1") (pintype "passive"))
      (node (ref "DA1") (pin "10") (pinfunction "REGOUT_10") (pintype "passive"))
    )
    (net (code "36") (name "Net-(DA1-nCS)") (class "Default")
      (node (ref "DA1") (pin "22") (pinfunction "nCS_22") (pintype "passive"))
      (node (ref "R5") (pin "2") (pinfunction "2_2") (pintype "passive"))
    )
    (net (code "37") (name "Net-(DA2-OSC_IN)") (class "Default")
      (node (ref "DA2") (pin "25") (pinfunction "OSC_IN_25") (pintype "passive"))
      (node (ref "Y2") (pin "4") (pinfunction "2_4") (pintype "passive"))
    )
    (net (code "38") (name "Net-(DA2-OSC_OUT)") (class "Default")
      (node (ref "DA2") (pin "24") (pinfunction "OSC_OUT_24") (pintype "passive"))
      (node (ref "Y2") (pin "2") (pinfunction "1_2") (pintype "passive"))
    )
    (net (code "39") (name "Net-(DA2-PC14{slash}CM4_EVENTOUT{slash}OSC32_IN)") (class "Default")
      (node (ref "C11") (pin "1") (pinfunction "1_1") (pintype "passive"))
      (node (ref "DA2") (pin "2") (pinfunction "PC14/CM4_EVENTOUT/OSC32_IN_2") (pintype "passive"))
      (node (ref "Y1") (pin "2") (pinfunction "2_2") (pintype "passive"))
    )
    (net (code "40") (name "Net-(DA2-PC15{slash}CM4_EVENTOUT{slash}OSC32_OUT)") (class "Default")
      (node (ref "C12") (pin "1") (pinfunction "1_1") (pintype "passive"))
      (node (ref "DA2") (pin "3") (pinfunction "PC15/CM4_EVENTOUT/OSC32_OUT_3") (pintype "passive"))
      (node (ref "Y1") (pin "1") (pinfunction "1_1") (pintype "passive"))
    )
    (net (code "41") (name "Net-(DA2-VLXSMPS)") (class "Default")
      (node (ref "DA2") (pin "33") (pinfunction "VLXSMPS_33") (pintype "passive"))
      (node (ref "L1") (pin "2") (pinfunction "2_2") (pintype "passive"))
    )
    (net (code "42") (name "Net-(L4-Pad2)") (class "Default")
      (node (ref "L4") (pin "2") (pinfunction "2_2") (pintype "passive"))
      (node (ref "L5") (pin "1") (pinfunction "1_1") (pintype "passive"))
    )
    (net (code "43") (name "Net-(T1-B)") (class "Default")
      (node (ref "R6") (pin "1") (pinfunction "1_1") (pintype "passive"))
      (node (ref "R7") (pin "2") (pinfunction "2_2") (pintype "passive"))
      (node (ref "T1") (pin "1") (pinfunction "B_1") (pintype "passive"))
    )
    (net (code "44") (name "Net-(T1-C)") (class "Default")
      (node (ref "R8") (pin "1") (pinfunction "1_1") (pintype "passive"))
      (node (ref "T1") (pin "3") (pinfunction "C_3") (pintype "passive"))
    )
    (net (code "45") (name "unconnected-(ANT1-1-Pad2)") (class "Default")
      (node (ref "ANT1") (pin "2") (pinfunction "1_2") (pintype "passive+no_connect"))
    )
    (net (code "46") (name "unconnected-(DA1-AUX_CL-Pad7)") (class "Default")
      (node (ref "DA1") (pin "7") (pinfunction "AUX_CL_7") (pintype "passive+no_connect"))
    )
    (net (code "47") (name "unconnected-(DA1-AUX_DA-Pad21)") (class "Default")
      (node (ref "DA1") (pin "21") (pinfunction "AUX_DA_21") (pintype "passive+no_connect"))
    )
    (net (code "48") (name "unconnected-(DA1-NC-Pad2)") (class "Default")
      (node (ref "DA1") (pin "2") (pinfunction "NC_2") (pintype "passive+no_connect"))
    )
    (net (code "49") (name "unconnected-(DA1-NC-Pad3)") (class "Default")
      (node (ref "DA1") (pin "3") (pinfunction "NC_3") (pintype "passive+no_connect"))
    )
    (net (code "50") (name "unconnected-(DA1-NC-Pad4)") (class "Default")
      (node (ref "DA1") (pin "4") (pinfunction "NC_4") (pintype "passive+no_connect"))
    )
    (net (code "51") (name "unconnected-(DA1-NC-Pad5)") (class "Default")
      (node (ref "DA1") (pin "5") (pinfunction "NC_5") (pintype "passive+no_connect"))
    )
    (net (code "52") (name "unconnected-(DA1-NC-Pad6)") (class "Default")
      (node (ref "DA1") (pin "6") (pinfunction "NC_6") (pintype "passive+no_connect"))
    )
    (net (code "53") (name "unconnected-(DA1-NC-Pad14)") (class "Default")
      (node (ref "DA1") (pin "14") (pinfunction "NC_14") (pintype "passive+no_connect"))
    )
    (net (code "54") (name "unconnected-(DA1-NC-Pad15)") (class "Default")
      (node (ref "DA1") (pin "15") (pinfunction "NC_15") (pintype "passive+no_connect"))
    )
    (net (code "55") (name "unconnected-(DA1-NC-Pad16)") (class "Default")
      (node (ref "DA1") (pin "16") (pinfunction "NC_16") (pintype "passive+no_connect"))
    )
    (net (code "56") (name "unconnected-(DA1-NC-Pad17)") (class "Default")
      (node (ref "DA1") (pin "17") (pinfunction "NC_17") (pintype "passive+no_connect"))
    )
    (net (code "57") (name "unconnected-(DA1-RESV(NC)-Pad19)") (class "Default")
      (node (ref "DA1") (pin "19") (pinfunction "RESV(NC)_19") (pintype "passive+no_connect"))
    )
    (net (code "58") (name "unconnected-(DA2-AT0-Pad26)") (class "Default")
      (node (ref "DA2") (pin "26") (pinfunction "AT0_26") (pintype "passive+no_connect"))
    )
    (net (code "59") (name "unconnected-(DA2-AT1-Pad27)") (class "Default")
      (node (ref "DA2") (pin "27") (pinfunction "AT1_27") (pintype "passive+no_connect"))
    )
    (net (code "60") (name "unconnected-(DA2-PA1{slash}TIM2_CH2{slash}I2C1_SMBA{slash}SPI1_SCK{slash}LCD_SEG0{slash}CM4_EVENTOUT{slash}COMP1_INP{slash}ADC1_IN6-Pad10)") (class "Default")
      (node (ref "DA2") (pin "10") (pinfunction "PA1/TIM2_CH2/I2C1_SMBA/SPI1_SCK/LCD_SEG0/CM4_EVENTOUT/COMP1_INP/ADC1_IN6_10") (pintype "passive+no_connect"))
    )
    (net (code "61") (name "unconnected-(DA2-PA4{slash}SPI1_NSS{slash}SAI1_FS_B{slash}LPTIM2_OUT{slash}LCD_SEG5{slash}CM4_EVENTOUT{slash}COMP1_INM{slash}COMP2_INM{slash}ADC1_IN9-Pad13)") (class "Default")
      (node (ref "DA2") (pin "13") (pinfunction "PA4/SPI1_NSS/SAI1_FS_B/LPTIM2_OUT/LCD_SEG5/CM4_EVENTOUT/COMP1_INM/COMP2_INM/ADC1_IN9_13") (pintype "passive"))
    )
    (net (code "62") (name "unconnected-(DA2-PA5{slash}TIM2_CH1{slash}TIM2_ETR{slash}SPI1_SCK{slash}LPTIM2_ETR{slash}SAI1_SD_B{slash}CM4_EVENTOUT{slash}COMP1_INM{slash}COMP2_INM{slash}ADC1_IN10-Pad14)") (class "Default")
      (node (ref "DA2") (pin "14") (pinfunction "PA5/TIM2_CH1/TIM2_ETR/SPI1_SCK/LPTIM2_ETR/SAI1_SD_B/CM4_EVENTOUT/COMP1_INM/COMP2_INM/ADC1_IN10_14") (pintype "passive"))
    )
    (net (code "63") (name "unconnected-(DA2-PA6{slash}IM1_BKIN{slash}SPI1_MISO{slash}LPUART1_CTS{slash}QUADSPI_BK1_IO3{slash}LCD_SEG3{slash}TIM16_CH1{slash}CM4_EVENTOUT{slash}ADC1_IN11-Pad15)") (class "Default")
      (node (ref "DA2") (pin "15") (pinfunction "PA6/IM1_BKIN/SPI1_MISO/LPUART1_CTS/QUADSPI_BK1_IO3/LCD_SEG3/TIM16_CH1/CM4_EVENTOUT/ADC1_IN11_15") (pintype "passive+no_connect"))
    )
    (net (code "64") (name "unconnected-(DA2-PA7{slash}IM1_CH1N{slash}I2C3_SCL{slash}SPI1_MOSI{slash}QUADSPI_BK1_IO2{slash}LCD_SEG4{slash}COMP2_OUT{slash}TIM17_CH1{slash}CM4_EVENTOUT{slash}ADC1_IN12-Pad16)") (class "Default")
      (node (ref "DA2") (pin "16") (pinfunction "PA7/IM1_CH1N/I2C3_SCL/SPI1_MOSI/QUADSPI_BK1_IO2/LCD_SEG4/COMP2_OUT/TIM17_CH1/CM4_EVENTOUT/ADC1_IN12_16") (pintype "passive"))
    )
    (net (code "65") (name "unconnected-(DA2-PA8{slash}MCO{slash}TIM1_CH1{slash}SAI1_PDM_CK2{slash}USART1_CK{slash}LCD_COM0{slash}SAI1_SCK_A{slash}LPTIM2_OUT{slash}CM4_EVENTOUT-Pad17)") (class "Default")
      (node (ref "DA2") (pin "17") (pinfunction "PA8/MCO/TIM1_CH1/SAI1_PDM_CK2/USART1_CK/LCD_COM0/SAI1_SCK_A/LPTIM2_OUT/CM4_EVENTOUT_17") (pintype "passive+no_connect"))
    )
    (net (code "66") (name "unconnected-(DA2-PA9{slash}TIM1_CH2{slash}SAI1_PDM_DI2{slash}I2C1_SCL{slash}SPI2_SCK{slash}USART1_TX{slash}LCD_COM1{slash}SAI1_FS_A{slash}CM4_EVENTOUT{slash}COMP1_INM{slash}ADC1_IN16-Pad18)") (class "Default")
      (node (ref "DA2") (pin "18") (pinfunction "PA9/TIM1_CH2/SAI1_PDM_DI2/I2C1_SCL/SPI2_SCK/USART1_TX/LCD_COM1/SAI1_FS_A/CM4_EVENTOUT/COMP1_INM/ADC1_IN16_18") (pintype "passive"))
    )
    (net (code "67") (name "unconnected-(DA2-PB2{slash}RTC_OUT{slash}LPTIM1_OUT{slash}I2C3_SMBA{slash}SPI1_NSS{slash}LCD_VLCD{slash}SAI1_EXTCLK{slash}CM4_EVENTOUT{slash}COMP1_INP-Pad19)") (class "Default")
      (node (ref "DA2") (pin "19") (pinfunction "PB2/RTC_OUT/LPTIM1_OUT/I2C3_SMBA/SPI1_NSS/LCD_VLCD/SAI1_EXTCLK/CM4_EVENTOUT/COMP1_INP_19") (pintype "passive"))
    )
  )
)
